# Estacion_Meteorologica_Feather__M0.net
KiCad netlist of a schematic drawn in Altium Designer
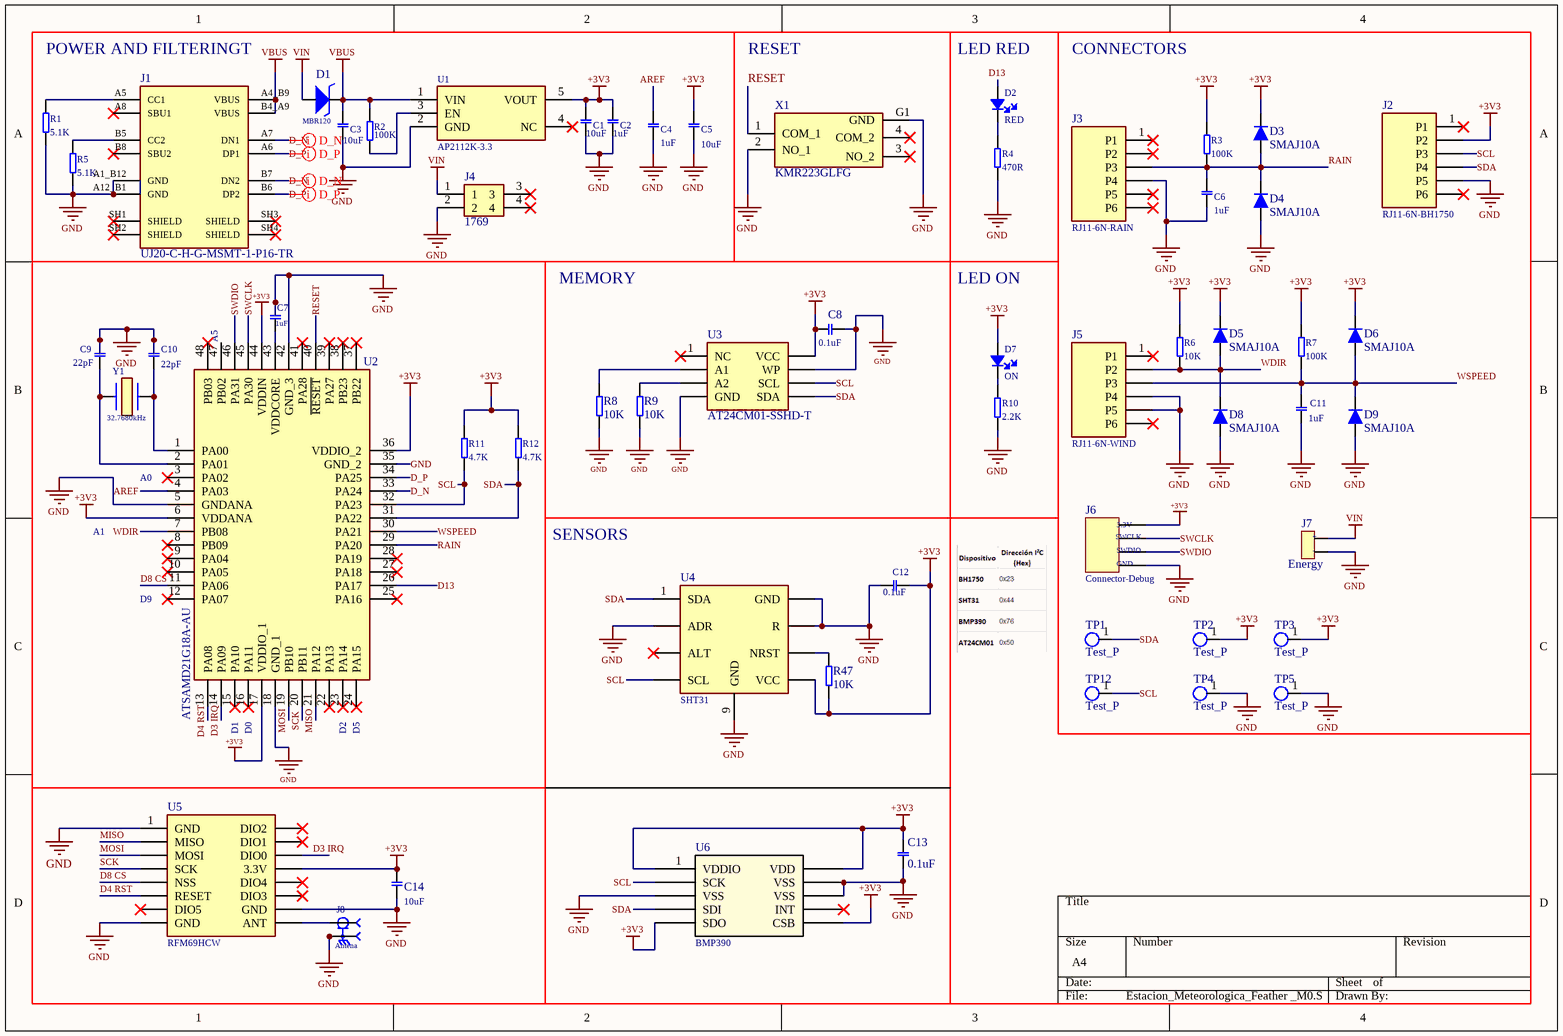
[diagram p0: Estacion_Meteorologica_Feather _M0.SchDoc]

(export (version "E")
  (design (tool "Eeschema 10.0.6"))
  (components
    (comp (ref "C1")
      (value "10uF")
      (footprint "CAPCP1608_0603")
      (description "Capacitor_10uF_0603")
      (libsource (lib "Estacion_Meteorologica_Final") (part "C0603X100J1GACAUTO"))
    )
    (comp (ref "C2")
      (value "1uF")
      (footprint "CAPCP1608_0603")
      (description "Capacitor_1uF_0603")
      (libsource (lib "Estacion_Meteorologica_Final") (part "C0603X105J4RACTU"))
    )
    (comp (ref "C3")
      (value "10uF")
      (footprint "CAPCP1608_0603")
      (description "Capacitor_10uF_0603")
      (libsource (lib "Estacion_Meteorologica_Final") (part "C0603X100J1GACAUTO"))
    )
    (comp (ref "C4")
      (value "1uF")
      (footprint "CAPCP1608_0603")
      (description "Capacitor_1uF_0603")
      (libsource (lib "Estacion_Meteorologica_Final") (part "C0603X105J4RACTU"))
    )
    (comp (ref "C5")
      (value "10uF")
      (footprint "CAPCP1608_0603")
      (description "Capacitor_10uF_0603")
      (libsource (lib "Estacion_Meteorologica_Final") (part "C0603X100J1GACAUTO"))
    )
    (comp (ref "C6")
      (value "1uF")
      (footprint "CAPCP1608_0603")
      (description "Capacitor_1uF_0603")
      (libsource (lib "Estacion_Meteorologica_Final") (part "C0603X105J4RACTU"))
    )
    (comp (ref "C7")
      (value "1uF")
      (footprint "CAPCP1608_0603")
      (description "Capacitor_1uF_0603")
      (libsource (lib "Estacion_Meteorologica_Final") (part "C0603X105J4RACTU"))
    )
    (comp (ref "C8")
      (value "0.1uF")
      (footprint "CAPCP1608_0603")
      (description "Capacitor_0.1uF_0603")
      (libsource (lib "Estacion_Meteorologica_Final") (part "06035C104K4T4A"))
    )
    (comp (ref "C9")
      (value "22pF")
      (footprint "CAPCP1608_0603")
      (description "Capacitor_22pF_0603")
      (libsource (lib "Estacion_Meteorologica_Final") (part "C0603C220J1GAC"))
    )
    (comp (ref "C10")
      (value "22pF")
      (footprint "CAPCP1608_0603")
      (description "Capacitor_22pF_0603")
      (libsource (lib "Estacion_Meteorologica_Final") (part "C0603C220J1GAC"))
    )
    (comp (ref "C11")
      (value "1uF")
      (footprint "CAPCP1608_0603")
      (description "Capacitor_1uF_0603")
      (libsource (lib "Estacion_Meteorologica_Final") (part "C0603X105J4RACTU"))
    )
    (comp (ref "C12")
      (value "0.1uF")
      (footprint "CAPCP1608_0603")
      (description "Capacitor_0.1uF_0603")
      (libsource (lib "Estacion_Meteorologica_Final") (part "06035C104K4T4A"))
    )
    (comp (ref "C13")
      (value "0.1uF")
      (footprint "CAPCP1608_0603")
      (description "Capacitor_0.1uF_0603")
      (libsource (lib "Estacion_Meteorologica_Final") (part "06035C104K4T4A"))
    )
    (comp (ref "C14")
      (value "10uF")
      (footprint "CAPCP1608_0603")
      (description "Capacitor_10uF_0603")
      (libsource (lib "Estacion_Meteorologica_Final") (part "C0603X100J1GACAUTO"))
    )
    (comp (ref "D1")
      (value "MBR120")
      (footprint "SODFL3616X98N")
      (description "Diodo_Zenner_Sod-123FL-2")
      (libsource (lib "Estacion_Meteorologica_Final") (part "MBR120ESFT3G"))
    )
    (comp (ref "D2")
      (value "RED")
      (footprint "DIODO_0603")
      (description "LED_NARANJA_0603")
      (libsource (lib "Estacion_Meteorologica_Final") (part "SML-D12D1WT86"))
    )
    (comp (ref "D3")
      (value "SMAJ10A")
      (footprint "DIOM4325X250N")
      (description "TVS Diode 10V 400W Unidirectional SMAJ10A (DO-214AC)")
      (libsource (lib "Estacion_Meteorologica_Final") (part "SMAJ10A"))
    )
    (comp (ref "D4")
      (value "SMAJ10A")
      (footprint "DIOM4325X250N")
      (description "TVS Diode 10V 400W Unidirectional SMAJ10A (DO-214AC)")
      (libsource (lib "Estacion_Meteorologica_Final") (part "SMAJ10A"))
    )
    (comp (ref "D5")
      (value "SMAJ10A")
      (footprint "DIOM4325X250N")
      (description "TVS Diode 10V 400W Unidirectional SMAJ10A (DO-214AC)")
      (libsource (lib "Estacion_Meteorologica_Final") (part "SMAJ10A"))
    )
    (comp (ref "D6")
      (value "SMAJ10A")
      (footprint "DIOM4325X250N")
      (description "TVS Diode 10V 400W Unidirectional SMAJ10A (DO-214AC)")
      (libsource (lib "Estacion_Meteorologica_Final") (part "SMAJ10A"))
    )
    (comp (ref "D7")
      (value "ON")
      (footprint "DIODO_0603")
      (description "LED_NARANJA_0603")
      (libsource (lib "Estacion_Meteorologica_Final") (part "SML-D12D1WT86"))
    )
    (comp (ref "D8")
      (value "SMAJ10A")
      (footprint "DIOM4325X250N")
      (description "TVS Diode 10V 400W Unidirectional SMAJ10A (DO-214AC)")
      (libsource (lib "Estacion_Meteorologica_Final") (part "SMAJ10A"))
    )
    (comp (ref "D9")
      (value "SMAJ10A")
      (footprint "DIOM4325X250N")
      (description "TVS Diode 10V 400W Unidirectional SMAJ10A (DO-214AC)")
      (libsource (lib "Estacion_Meteorologica_Final") (part "SMAJ10A"))
    )
    (comp (ref "J1")
      (value "UJ20-C-H-G-MSMT-1-P16-TR")
      (footprint "uJ20-C-H-G-MSMT-1-P16-TR")
      (description "Conector usb c")
      (libsource (lib "Estacion_Meteorologica_Final") (part "UJ20-C-H-G-MSMT-1-P16-TR"))
    )
    (comp (ref "J2")
      (value "RJ11-6N-BH1750")
      (footprint "TE_RJ11-6N-B")
      (description "6 Position 1 Port Right Angle RJ11 Low Profile Filtered EMI/RFI Modular Jack")
      (fields (field (name "MP") "RJ11-6N-B") (field (name "MF") "TE Connectivity"))
      (libsource (lib "Estacion_Meteorologica_Final") (part "RJ11-6N-B"))
    )
    (comp (ref "J3")
      (value "RJ11-6N-RAIN")
      (footprint "TE_RJ11-6N-B")
      (description "6 Position 1 Port Right Angle RJ11 Low Profile Filtered EMI/RFI Modular Jack")
      (fields (field (name "MP") "RJ11-6N-B") (field (name "MF") "TE Connectivity"))
      (libsource (lib "Estacion_Meteorologica_Final") (part "RJ11-6N-B"))
    )
    (comp (ref "J4")
      (value "1769")
      (footprint "1769_Conector_Bateria")
      (description "Adafruit Accessories JST-PH 2-pin SMT Right Angle Connect")
      (fields (field (name "MOUSER PART NUMBER") "485-1769"))
      (libsource (lib "Estacion_Meteorologica_Final") (part "1769"))
    )
    (comp (ref "J5")
      (value "RJ11-6N-WIND")
      (footprint "TE_RJ11-6N-B")
      (description "6 Position 1 Port Right Angle RJ11 Low Profile Filtered EMI/RFI Modular Jack")
      (fields (field (name "MP") "RJ11-6N-B") (field (name "MF") "TE Connectivity"))
      (libsource (lib "Estacion_Meteorologica_Final") (part "RJ11-6N-B"))
    )
    (comp (ref "J6")
      (value "Connector-Debug")
      (footprint "HDR1X4")
      (libsource (lib "Estacion_Meteorologica_Final") (part "Connector_04_debug"))
    )
    (comp (ref "J7")
      (value "Energy")
      (footprint "HDR1X2_2")
      (description "Conector de gestor de carga")
      (libsource (lib "Estacion_Meteorologica_Final") (part "Connector_energy"))
    )
    (comp (ref "J8")
      (value "Antena")
      (footprint "SAMTEC_RSP-122811-01")
      (description "U.FL (UMCC), IPEX MHF1 Connector Receptacle, Male Pin 50Ohm Surface Mount Solder")
      (fields (field (name "MP") "RSP-122811-01"))
      (libsource (lib "Estacion_Meteorologica_Final") (part "RSP-122811-01"))
    )
    (comp (ref "R1")
      (value "5.1K")
      (footprint "RESC1608_0603")
      (description "Resistencia_5.1K_0603")
      (libsource (lib "Estacion_Meteorologica_Final") (part "RCA06035K10JNEA"))
    )
    (comp (ref "R2")
      (value "100K")
      (footprint "RESC1608_0603")
      (description "Resistencia_100K_0603")
      (libsource (lib "Estacion_Meteorologica_Final") (part "RCA0603100KFKEAHP"))
    )
    (comp (ref "R3")
      (value "100K")
      (footprint "RESC1608_0603")
      (description "Resistencia_100K_0603")
      (libsource (lib "Estacion_Meteorologica_Final") (part "RCA0603100KFKEAHP"))
    )
    (comp (ref "R4")
      (value "470R")
      (footprint "RESC1608_0603")
      (description "Resistencia_470R_0603")
      (libsource (lib "Estacion_Meteorologica_Final") (part "RCA0603470RFKEA"))
    )
    (comp (ref "R5")
      (value "5.1K")
      (footprint "RESC1608_0603")
      (description "Resistencia_5.1K_0603")
      (libsource (lib "Estacion_Meteorologica_Final") (part "RCA06035K10JNEA"))
    )
    (comp (ref "R6")
      (value "10K")
      (footprint "RESC1608_0603")
      (description "Resistencia_10K_0603")
      (libsource (lib "Estacion_Meteorologica_Final") (part "RCA060310K0JNEA"))
    )
    (comp (ref "R7")
      (value "100K")
      (footprint "RESC1608_0603")
      (description "Resistencia_100K_0603")
      (libsource (lib "Estacion_Meteorologica_Final") (part "RCA0603100KFKEAHP"))
    )
    (comp (ref "R8")
      (value "10K")
      (footprint "RESC1608_0603")
      (description "Resistencia_10K_0603")
      (libsource (lib "Estacion_Meteorologica_Final") (part "RCA060310K0JNEA"))
    )
    (comp (ref "R9")
      (value "10K")
      (footprint "RESC1608_0603")
      (description "Resistencia_10K_0603")
      (libsource (lib "Estacion_Meteorologica_Final") (part "RCA060310K0JNEA"))
    )
    (comp (ref "R10")
      (value "2.2K")
      (footprint "RESC1608_0603")
      (description "Resistencia_2.2K_0603")
      (libsource (lib "Estacion_Meteorologica_Final") (part "RCA06032K21FKTA"))
    )
    (comp (ref "R11")
      (value "4.7K")
      (footprint "RESC1608_0603")
      (description "Resistencia_4.7K_0603")
      (libsource (lib "Estacion_Meteorologica_Final") (part "RCA06034K70FKEA"))
    )
    (comp (ref "R12")
      (value "4.7K")
      (footprint "RESC1608_0603")
      (description "Resistencia_4.7K_0603")
      (libsource (lib "Estacion_Meteorologica_Final") (part "RCA06034K70FKEA"))
    )
    (comp (ref "R47")
      (value "10K")
      (footprint "RESC1608_0603")
      (description "Resistencia_10K_0603")
      (libsource (lib "Estacion_Meteorologica_Final") (part "RCA060310K0JNEA"))
    )
    (comp (ref "TP1")
      (value "Test_P")
      (footprint "Test_point")
      (libsource (lib "Estacion_Meteorologica_Final") (part "Test_point"))
    )
    (comp (ref "TP2")
      (value "Test_P")
      (footprint "Test_point")
      (libsource (lib "Estacion_Meteorologica_Final") (part "Test_point"))
    )
    (comp (ref "TP3")
      (value "Test_P")
      (footprint "Test_point")
      (libsource (lib "Estacion_Meteorologica_Final") (part "Test_point"))
    )
    (comp (ref "TP4")
      (value "Test_P")
      (footprint "Test_point")
      (libsource (lib "Estacion_Meteorologica_Final") (part "Test_point"))
    )
    (comp (ref "TP5")
      (value "Test_P")
      (footprint "Test_point")
      (libsource (lib "Estacion_Meteorologica_Final") (part "Test_point"))
    )
    (comp (ref "TP12")
      (value "Test_P")
      (footprint "Test_point")
      (libsource (lib "Estacion_Meteorologica_Final") (part "Test_point"))
    )
    (comp (ref "U1")
      (value "AP2112K-3.3")
      (footprint "SOT-23-5")
      (fields
        (field (name "MOUSER PART NUMBER") "621-AP2112K-3.3TRG1")
        (field (name "MANUFACTURER_PART_NUMBER") "AP2112K-3.3TRG1")
      )
      (libsource (lib "Estacion_Meteorologica_Final") (part "AP2112K-3.3TRG1"))
    )
    (comp (ref "U2")
      (value "ATSAMD21G18A-AU")
      (footprint "QFP-48N")
      (description "ARM Microcontrollers - MCU 256KB 32KB 48TQFP GRN1.6-3.6V48MHz")
      (fields (field (name "MOUSER PART NUMBER") "556-ATSAMD21G18A-AU"))
      (libsource (lib "Estacion_Meteorologica_Final") (part "ATSAMD21G18A-AU"))
    )
    (comp (ref "U3")
      (value "AT24CM01-SSHD-T")
      (footprint "SOIC-8N")
      (description "EEPROM SERIAL EEPROM, 1M 2-WIR-8 SOIC")
      (fields (field (name "MOUSER PART NUMBER") "556-AT24CM01-SSHD-T"))
      (libsource (lib "Estacion_Meteorologica_Final") (part "AT24CM01-SSHD-T"))
    )
    (comp (ref "U4")
      (value "SHT31")
      (footprint "SON50P250X250X90-9T110X180N")
      (description "Humidity Temperature Sensor 0 ~ 100% RH Analog Voltage Â±2% RH 8s Surface Mount")
      (fields (field (name "MF") "Sensirion AG"))
      (libsource (lib "Estacion_Meteorologica_Final") (part "SHT31"))
    )
    (comp (ref "U5")
      (value "RFM69HCW")
      (footprint "COM-13909")
      (description "Rfm69hcw Wireless Transceiver 91")
      (fields (field (name "MP") "COM-13909"))
      (libsource (lib "Estacion_Meteorologica_Final") (part "COM-13909"))
    )
    (comp (ref "U6")
      (value "BMP390")
      (footprint "10LGA_2X2X0p75_BOS-M")
      (description "Barometric Pressure Sensor, I2C/SPI, 300-1250 hPa")
      (libsource (lib "Estacion_Meteorologica_Final") (part "BMP390"))
    )
    (comp (ref "X1")
      (value "KMR223GLFG")
      (footprint "KMR223GLFG_Boton")
      (description "Tactile Switch SPST-NO Top Actuated Surface Mount")
      (fields (field (name "MOUSER PART NUMBER") "611-KMR223GLFG"))
      (libsource (lib "Estacion_Meteorologica_Final") (part "KMR223GLFG_1"))
    )
    (comp (ref "Y1")
      (value "32.7680kHz")
      (footprint "XTAL 830050789")
      (description "XTAL 32.7680kHz 20ppm 2.0 x 1.2mm")
      (libsource (lib "Estacion_Meteorologica_Final") (part "830050789"))
    )
  )
  (nets
    (net (code "1") (name "+3V3") (class "Default")
      (node (ref "C1") (pin "2") (pinfunction "2_2") (pintype "passive"))
      (node (ref "C12") (pin "2") (pinfunction "2_2") (pintype "passive"))
      (node (ref "C13") (pin "2") (pinfunction "2_2") (pintype "passive"))
      (node (ref "C14") (pin "2") (pinfunction "2_2") (pintype "passive"))
      (node (ref "C2") (pin "2") (pinfunction "2_2") (pintype "passive"))
      (node (ref "C5") (pin "2") (pinfunction "2_2") (pintype "passive"))
      (node (ref "C8") (pin "1") (pinfunction "1_1") (pintype "passive"))
      (node (ref "D3") (pin "2") (pinfunction "2_2") (pintype "passive"))
      (node (ref "D5") (pin "2") (pinfunction "2_2") (pintype "passive"))
      (node (ref "D6") (pin "2") (pinfunction "2_2") (pintype "passive"))
      (node (ref "D7") (pin "1") (pinfunction "1_1") (pintype "passive"))
      (node (ref "J2") (pin "2") (pinfunction "P2_2") (pintype "passive"))
      (node (ref "J6") (pin "1") (pinfunction "1_1") (pintype "passive"))
      (node (ref "R11") (pin "2") (pinfunction "2_2") (pintype "passive"))
      (node (ref "R12") (pin "2") (pinfunction "2_2") (pintype "passive"))
      (node (ref "R3") (pin "2") (pinfunction "2_2") (pintype "passive"))
      (node (ref "R47") (pin "1") (pinfunction "1_1") (pintype "passive"))
      (node (ref "R6") (pin "2") (pinfunction "2_2") (pintype "passive"))
      (node (ref "R7") (pin "2") (pinfunction "2_2") (pintype "passive"))
      (node (ref "TP2") (pin "1") (pinfunction "1_1") (pintype "passive"))
      (node (ref "TP3") (pin "1") (pinfunction "1_1") (pintype "passive"))
      (node (ref "U1") (pin "5") (pinfunction "VOUT_5") (pintype "passive"))
      (node (ref "U2") (pin "17") (pinfunction "VDDIO_1_17") (pintype "passive"))
      (node (ref "U2") (pin "36") (pinfunction "VDDIO_2_36") (pintype "passive"))
      (node (ref "U2") (pin "44") (pinfunction "VDDIN_44") (pintype "passive"))
      (node (ref "U2") (pin "6") (pinfunction "VDDANA_6") (pintype "passive"))
      (node (ref "U3") (pin "8") (pinfunction "VCC_8") (pintype "passive"))
      (node (ref "U4") (pin "5") (pinfunction "VCC_5") (pintype "passive"))
      (node (ref "U5") (pin "13") (pinfunction "3.3V_13") (pintype "passive"))
      (node (ref "U6") (pin "1") (pinfunction "VDDIO_1") (pintype "passive"))
      (node (ref "U6") (pin "10") (pinfunction "VDD_10") (pintype "passive"))
      (node (ref "U6") (pin "5") (pinfunction "SDO_5") (pintype "passive"))
      (node (ref "U6") (pin "6") (pinfunction "CSB_6") (pintype "passive"))
    )
    (net (code "2") (name "/AREF") (class "Default")
      (node (ref "C4") (pin "2") (pinfunction "2_2") (pintype "passive"))
      (node (ref "U2") (pin "4") (pinfunction "PA03_4") (pintype "passive"))
    )
    (net (code "3") (name "/D3 IRQ") (class "Default")
      (node (ref "U2") (pin "14") (pinfunction "PA09_14") (pintype "passive"))
      (node (ref "U5") (pin "14") (pinfunction "DIO0_14") (pintype "passive"))
    )
    (net (code "4") (name "/D4 RST") (class "Default")
      (node (ref "U2") (pin "13") (pinfunction "PA08_13") (pintype "passive"))
      (node (ref "U5") (pin "6") (pinfunction "RESET_6") (pintype "passive"))
    )
    (net (code "5") (name "/D8 CS") (class "Default")
      (node (ref "U2") (pin "11") (pinfunction "PA06_11") (pintype "passive"))
      (node (ref "U5") (pin "5") (pinfunction "NSS_5") (pintype "passive"))
    )
    (net (code "6") (name "/D13") (class "Default")
      (node (ref "D2") (pin "1") (pinfunction "1_1") (pintype "passive"))
      (node (ref "U2") (pin "26") (pinfunction "PA17_26") (pintype "passive"))
    )
    (net (code "7") (name "/D_N") (class "Default")
      (node (ref "J1") (pin "A7") (pinfunction "DN1_A7") (pintype "passive"))
      (node (ref "J1") (pin "B7") (pinfunction "DN2_B7") (pintype "passive"))
      (node (ref "U2") (pin "33") (pinfunction "PA24_33") (pintype "passive"))
    )
    (net (code "8") (name "/D_P") (class "Default")
      (node (ref "J1") (pin "A6") (pinfunction "DP1_A6") (pintype "passive"))
      (node (ref "J1") (pin "B6") (pinfunction "DP2_B6") (pintype "passive"))
      (node (ref "U2") (pin "34") (pinfunction "PA25_34") (pintype "passive"))
    )
    (net (code "9") (name "/MISO") (class "Default")
      (node (ref "U2") (pin "21") (pinfunction "PA12_21") (pintype "passive"))
      (node (ref "U5") (pin "2") (pinfunction "MISO_2") (pintype "passive"))
    )
    (net (code "10") (name "/MOSI") (class "Default")
      (node (ref "U2") (pin "19") (pinfunction "PB10_19") (pintype "passive"))
      (node (ref "U5") (pin "3") (pinfunction "MOSI_3") (pintype "passive"))
    )
    (net (code "11") (name "/RAIN") (class "Default")
      (node (ref "C6") (pin "2") (pinfunction "2_2") (pintype "passive"))
      (node (ref "D3") (pin "1") (pinfunction "21_1") (pintype "passive"))
      (node (ref "D4") (pin "2") (pinfunction "2_2") (pintype "passive"))
      (node (ref "J3") (pin "3") (pinfunction "P3_3") (pintype "passive"))
      (node (ref "R3") (pin "1") (pinfunction "1_1") (pintype "passive"))
      (node (ref "U2") (pin "29") (pinfunction "PA20_29") (pintype "passive"))
    )
    (net (code "12") (name "/RESET") (class "Default")
      (node (ref "U2") (pin "40") (pinfunction "~{RESET}_40") (pintype "passive"))
      (node (ref "X1") (pin "1") (pinfunction "COM_1_1") (pintype "passive"))
    )
    (net (code "13") (name "/SCK") (class "Default")
      (node (ref "U2") (pin "20") (pinfunction "PB11_20") (pintype "passive"))
      (node (ref "U5") (pin "4") (pinfunction "SCK_4") (pintype "passive"))
    )
    (net (code "14") (name "/SCL") (class "Default")
      (node (ref "J2") (pin "3") (pinfunction "P3_3") (pintype "passive"))
      (node (ref "R11") (pin "1") (pinfunction "1_1") (pintype "passive"))
      (node (ref "TP12") (pin "1") (pinfunction "1_1") (pintype "passive"))
      (node (ref "U2") (pin "32") (pinfunction "PA23_32") (pintype "passive"))
      (node (ref "U3") (pin "6") (pinfunction "SCL_6") (pintype "passive"))
      (node (ref "U4") (pin "4") (pinfunction "SCL_4") (pintype "passive"))
      (node (ref "U6") (pin "2") (pinfunction "SCK_2") (pintype "passive"))
    )
    (net (code "15") (name "/SDA") (class "Default")
      (node (ref "J2") (pin "4") (pinfunction "P4_4") (pintype "passive"))
      (node (ref "R12") (pin "1") (pinfunction "1_1") (pintype "passive"))
      (node (ref "TP1") (pin "1") (pinfunction "1_1") (pintype "passive"))
      (node (ref "U2") (pin "31") (pinfunction "PA22_31") (pintype "passive"))
      (node (ref "U3") (pin "5") (pinfunction "SDA_5") (pintype "passive"))
      (node (ref "U4") (pin "1") (pinfunction "SDA_1") (pintype "passive"))
      (node (ref "U6") (pin "4") (pinfunction "SDI_4") (pintype "passive"))
    )
    (net (code "16") (name "/SWCLK") (class "Default")
      (node (ref "J6") (pin "2") (pinfunction "2_2") (pintype "passive"))
      (node (ref "U2") (pin "45") (pinfunction "PA30_45") (pintype "passive"))
    )
    (net (code "17") (name "/SWDIO") (class "Default")
      (node (ref "J6") (pin "3") (pinfunction "3_3") (pintype "passive"))
      (node (ref "U2") (pin "46") (pinfunction "PA31_46") (pintype "passive"))
    )
    (net (code "18") (name "/WDIR") (class "Default")
      (node (ref "D5") (pin "1") (pinfunction "21_1") (pintype "passive"))
      (node (ref "D8") (pin "2") (pinfunction "2_2") (pintype "passive"))
      (node (ref "J5") (pin "2") (pinfunction "P2_2") (pintype "passive"))
      (node (ref "R6") (pin "1") (pinfunction "1_1") (pintype "passive"))
      (node (ref "U2") (pin "7") (pinfunction "PB08_7") (pintype "passive"))
    )
    (net (code "19") (name "/WSPEED") (class "Default")
      (node (ref "C11") (pin "2") (pinfunction "2_2") (pintype "passive"))
      (node (ref "D6") (pin "1") (pinfunction "21_1") (pintype "passive"))
      (node (ref "D9") (pin "2") (pinfunction "2_2") (pintype "passive"))
      (node (ref "J5") (pin "3") (pinfunction "P3_3") (pintype "passive"))
      (node (ref "R7") (pin "1") (pinfunction "1_1") (pintype "passive"))
      (node (ref "U2") (pin "30") (pinfunction "PA21_30") (pintype "passive"))
    )
    (net (code "20") (name "GND") (class "Default")
      (node (ref "C1") (pin "1") (pinfunction "1_1") (pintype "passive"))
      (node (ref "C10") (pin "2") (pinfunction "2_2") (pintype "passive"))
      (node (ref "C11") (pin "1") (pinfunction "1_1") (pintype "passive"))
      (node (ref "C12") (pin "1") (pinfunction "1_1") (pintype "passive"))
      (node (ref "C13") (pin "1") (pinfunction "1_1") (pintype "passive"))
      (node (ref "C14") (pin "1") (pinfunction "1_1") (pintype "passive"))
      (node (ref "C2") (pin "1") (pinfunction "1_1") (pintype "passive"))
      (node (ref "C3") (pin "1") (pinfunction "1_1") (pintype "passive"))
      (node (ref "C4") (pin "1") (pinfunction "1_1") (pintype "passive"))
      (node (ref "C5") (pin "1") (pinfunction "1_1") (pintype "passive"))
      (node (ref "C6") (pin "1") (pinfunction "1_1") (pintype "passive"))
      (node (ref "C7") (pin "2") (pinfunction "2_2") (pintype "passive"))
      (node (ref "C8") (pin "2") (pinfunction "2_2") (pintype "passive"))
      (node (ref "C9") (pin "2") (pinfunction "2_2") (pintype "passive"))
      (node (ref "D4") (pin "1") (pinfunction "21_1") (pintype "passive"))
      (node (ref "D8") (pin "1") (pinfunction "21_1") (pintype "passive"))
      (node (ref "D9") (pin "1") (pinfunction "21_1") (pintype "passive"))
      (node (ref "J1") (pin "A12_B1") (pinfunction "GND_A12_B1") (pintype "passive"))
      (node (ref "J1") (pin "A1_B12") (pinfunction "GND_A1_B12") (pintype "passive"))
      (node (ref "J2") (pin "5") (pinfunction "P5_5") (pintype "passive"))
      (node (ref "J3") (pin "4") (pinfunction "P4_4") (pintype "passive"))
      (node (ref "J4") (pin "2") (pinfunction "2_2") (pintype "passive"))
      (node (ref "J5") (pin "4") (pinfunction "P4_4") (pintype "passive"))
      (node (ref "J5") (pin "5") (pinfunction "P5_5") (pintype "passive"))
      (node (ref "J6") (pin "4") (pinfunction "4_4") (pintype "passive"))
      (node (ref "J7") (pin "2") (pinfunction "2_2") (pintype "passive"))
      (node (ref "J8") (pin "G1") (pinfunction "GND_G1") (pintype "passive"))
      (node (ref "J8") (pin "G2") (pinfunction "GND_G2") (pintype "passive"))
      (node (ref "R1") (pin "1") (pinfunction "1_1") (pintype "passive"))
      (node (ref "R10") (pin "2") (pinfunction "2_2") (pintype "passive"))
      (node (ref "R4") (pin "1") (pinfunction "1_1") (pintype "passive"))
      (node (ref "R5") (pin "1") (pinfunction "1_1") (pintype "passive"))
      (node (ref "R8") (pin "1") (pinfunction "1_1") (pintype "passive"))
      (node (ref "R9") (pin "1") (pinfunction "1_1") (pintype "passive"))
      (node (ref "TP4") (pin "1") (pinfunction "1_1") (pintype "passive"))
      (node (ref "TP5") (pin "1") (pinfunction "1_1") (pintype "passive"))
      (node (ref "U1") (pin "2") (pinfunction "GND_2") (pintype "passive"))
      (node (ref "U2") (pin "18") (pinfunction "GND_1_18") (pintype "passive"))
      (node (ref "U2") (pin "35") (pinfunction "GND_2_35") (pintype "passive"))
      (node (ref "U2") (pin "42") (pinfunction "GND_3_42") (pintype "passive"))
      (node (ref "U2") (pin "5") (pinfunction "GNDANA_5") (pintype "passive"))
      (node (ref "U3") (pin "4") (pinfunction "GND_4") (pintype "passive"))
      (node (ref "U3") (pin "7") (pinfunction "WP_7") (pintype "passive"))
      (node (ref "U4") (pin "2") (pinfunction "ADR_2") (pintype "passive"))
      (node (ref "U4") (pin "7") (pinfunction "R_7") (pintype "passive"))
      (node (ref "U4") (pin "8") (pinfunction "GND_8") (pintype "passive"))
      (node (ref "U4") (pin "9") (pinfunction "GND_9") (pintype "passive"))
      (node (ref "U5") (pin "1") (pinfunction "GND_1") (pintype "passive"))
      (node (ref "U5") (pin "10") (pinfunction "GND_10") (pintype "passive"))
      (node (ref "U5") (pin "8") (pinfunction "GND_8") (pintype "passive"))
      (node (ref "U6") (pin "3") (pinfunction "VSS_3") (pintype "passive"))
      (node (ref "U6") (pin "8") (pinfunction "VSS_8") (pintype "passive"))
      (node (ref "U6") (pin "9") (pinfunction "VSS_9") (pintype "passive"))
      (node (ref "X1") (pin "2") (pinfunction "NO_1_2") (pintype "passive"))
      (node (ref "X1") (pin "G1") (pinfunction "GND_G1") (pintype "passive"))
    )
    (net (code "21") (name "Net-(D2-Pad2)") (class "Default")
      (node (ref "D2") (pin "2") (pinfunction "2_2") (pintype "passive"))
      (node (ref "R4") (pin "2") (pinfunction "2_2") (pintype "passive"))
    )
    (net (code "22") (name "Net-(D7-Pad2)") (class "Default")
      (node (ref "D7") (pin "2") (pinfunction "2_2") (pintype "passive"))
      (node (ref "R10") (pin "1") (pinfunction "1_1") (pintype "passive"))
    )
    (net (code "23") (name "Net-(J1-CC1)") (class "Default")
      (node (ref "J1") (pin "A5") (pinfunction "CC1_A5") (pintype "passive"))
      (node (ref "R1") (pin "2") (pinfunction "2_2") (pintype "passive"))
    )
    (net (code "24") (name "Net-(J1-CC2)") (class "Default")
      (node (ref "J1") (pin "B5") (pinfunction "CC2_B5") (pintype "passive"))
      (node (ref "R5") (pin "2") (pinfunction "2_2") (pintype "passive"))
    )
    (net (code "25") (name "Net-(U1-EN)") (class "Default")
      (node (ref "R2") (pin "1") (pinfunction "1_1") (pintype "passive"))
      (node (ref "U1") (pin "3") (pinfunction "EN_3") (pintype "passive"))
    )
    (net (code "26") (name "Net-(U2-PA00)") (class "Default")
      (node (ref "C10") (pin "1") (pinfunction "1_1") (pintype "passive"))
      (node (ref "U2") (pin "1") (pinfunction "PA00_1") (pintype "passive"))
      (node (ref "Y1") (pin "2") (pinfunction "2_2") (pintype "passive"))
    )
    (net (code "27") (name "Net-(U2-PA01)") (class "Default")
      (node (ref "C9") (pin "1") (pinfunction "1_1") (pintype "passive"))
      (node (ref "U2") (pin "2") (pinfunction "PA01_2") (pintype "passive"))
      (node (ref "Y1") (pin "1") (pinfunction "1_1") (pintype "passive"))
    )
    (net (code "28") (name "Net-(U2-VDDCORE)") (class "Default")
      (node (ref "C7") (pin "1") (pinfunction "1_1") (pintype "passive"))
      (node (ref "U2") (pin "43") (pinfunction "VDDCORE_43") (pintype "passive"))
    )
    (net (code "29") (name "Net-(U3-A1)") (class "Default")
      (node (ref "R8") (pin "2") (pinfunction "2_2") (pintype "passive"))
      (node (ref "U3") (pin "2") (pinfunction "A1_2") (pintype "passive"))
    )
    (net (code "30") (name "Net-(U3-A2)") (class "Default")
      (node (ref "R9") (pin "2") (pinfunction "2_2") (pintype "passive"))
      (node (ref "U3") (pin "3") (pinfunction "A2_3") (pintype "passive"))
    )
    (net (code "31") (name "Net-(U4-NRST)") (class "Default")
      (node (ref "R47") (pin "2") (pinfunction "2_2") (pintype "passive"))
      (node (ref "U4") (pin "6") (pinfunction "NRST_6") (pintype "passive"))
    )
    (net (code "32") (name "Net-(U5-ANT)") (class "Default")
      (node (ref "J8") (pin "1") (pinfunction "1_1") (pintype "passive"))
      (node (ref "U5") (pin "9") (pinfunction "ANT_9") (pintype "passive"))
    )
    (net (code "33") (name "VBUS") (class "Default")
      (node (ref "C3") (pin "2") (pinfunction "2_2") (pintype "passive"))
      (node (ref "D1") (pin "2") (pinfunction "2_2") (pintype "passive"))
      (node (ref "J1") (pin "A4_B9") (pinfunction "VBUS_A4_B9") (pintype "passive"))
      (node (ref "J1") (pin "B4_A9") (pinfunction "VBUS_B4_A9") (pintype "passive"))
      (node (ref "R2") (pin "2") (pinfunction "2_2") (pintype "passive"))
      (node (ref "U1") (pin "1") (pinfunction "VIN_1") (pintype "passive"))
    )
    (net (code "34") (name "VIN") (class "Default")
      (node (ref "D1") (pin "1") (pinfunction "1_1") (pintype "passive"))
      (node (ref "J4") (pin "1") (pinfunction "1_1") (pintype "passive"))
      (node (ref "J7") (pin "1") (pinfunction "1_1") (pintype "passive"))
    )
    (net (code "35") (name "unconnected-(J1-SBU1-PadA8)") (class "Default")
      (node (ref "J1") (pin "A8") (pinfunction "SBU1_A8") (pintype "passive+no_connect"))
    )
    (net (code "36") (name "unconnected-(J1-SBU2-PadB8)") (class "Default")
      (node (ref "J1") (pin "B8") (pinfunction "SBU2_B8") (pintype "passive+no_connect"))
    )
    (net (code "37") (name "unconnected-(J1-SHIELD-PadSH1)") (class "Default")
      (node (ref "J1") (pin "SH1") (pinfunction "SHIELD_SH1") (pintype "passive+no_connect"))
    )
    (net (code "38") (name "unconnected-(J1-SHIELD-PadSH2)") (class "Default")
      (node (ref "J1") (pin "SH2") (pinfunction "SHIELD_SH2") (pintype "passive+no_connect"))
    )
    (net (code "39") (name "unconnected-(J1-SHIELD-PadSH3)") (class "Default")
      (node (ref "J1") (pin "SH3") (pinfunction "SHIELD_SH3") (pintype "passive+no_connect"))
    )
    (net (code "40") (name "unconnected-(J1-SHIELD-PadSH4)") (class "Default")
      (node (ref "J1") (pin "SH4") (pinfunction "SHIELD_SH4") (pintype "passive+no_connect"))
    )
    (net (code "41") (name "unconnected-(J2-P1-Pad1)") (class "Default")
      (node (ref "J2") (pin "1") (pinfunction "P1_1") (pintype "passive+no_connect"))
    )
    (net (code "42") (name "unconnected-(J2-P6-Pad6)") (class "Default")
      (node (ref "J2") (pin "6") (pinfunction "P6_6") (pintype "passive+no_connect"))
    )
    (net (code "43") (name "unconnected-(J3-P1-Pad1)") (class "Default")
      (node (ref "J3") (pin "1") (pinfunction "P1_1") (pintype "passive+no_connect"))
    )
    (net (code "44") (name "unconnected-(J3-P2-Pad2)") (class "Default")
      (node (ref "J3") (pin "2") (pinfunction "P2_2") (pintype "passive+no_connect"))
    )
    (net (code "45") (name "unconnected-(J3-P5-Pad5)") (class "Default")
      (node (ref "J3") (pin "5") (pinfunction "P5_5") (pintype "passive+no_connect"))
    )
    (net (code "46") (name "unconnected-(J3-P6-Pad6)") (class "Default")
      (node (ref "J3") (pin "6") (pinfunction "P6_6") (pintype "passive+no_connect"))
    )
    (net (code "47") (name "unconnected-(J4-Pad3)") (class "Default")
      (node (ref "J4") (pin "3") (pinfunction "3_3") (pintype "passive+no_connect"))
    )
    (net (code "48") (name "unconnected-(J4-Pad4)") (class "Default")
      (node (ref "J4") (pin "4") (pinfunction "4_4") (pintype "passive+no_connect"))
    )
    (net (code "49") (name "unconnected-(J5-P1-Pad1)") (class "Default")
      (node (ref "J5") (pin "1") (pinfunction "P1_1") (pintype "passive+no_connect"))
    )
    (net (code "50") (name "unconnected-(J5-P6-Pad6)") (class "Default")
      (node (ref "J5") (pin "6") (pinfunction "P6_6") (pintype "passive+no_connect"))
    )
    (net (code "51") (name "unconnected-(U1-NC-Pad4)") (class "Default")
      (node (ref "U1") (pin "4") (pinfunction "NC_4") (pintype "passive+no_connect"))
    )
    (net (code "52") (name "unconnected-(U2-PA02-Pad3)") (class "Default")
      (node (ref "U2") (pin "3") (pinfunction "PA02_3") (pintype "passive+no_connect"))
    )
    (net (code "53") (name "unconnected-(U2-PA04-Pad9)") (class "Default")
      (node (ref "U2") (pin "9") (pinfunction "PA04_9") (pintype "passive+no_connect"))
    )
    (net (code "54") (name "unconnected-(U2-PA05-Pad10)") (class "Default")
      (node (ref "U2") (pin "10") (pinfunction "PA05_10") (pintype "passive+no_connect"))
    )
    (net (code "55") (name "unconnected-(U2-PA07-Pad12)") (class "Default")
      (node (ref "U2") (pin "12") (pinfunction "PA07_12") (pintype "passive+no_connect"))
    )
    (net (code "56") (name "unconnected-(U2-PA10-Pad15)") (class "Default")
      (node (ref "U2") (pin "15") (pinfunction "PA10_15") (pintype "passive+no_connect"))
    )
    (net (code "57") (name "unconnected-(U2-PA11-Pad16)") (class "Default")
      (node (ref "U2") (pin "16") (pinfunction "PA11_16") (pintype "passive+no_connect"))
    )
    (net (code "58") (name "unconnected-(U2-PA13-Pad22)") (class "Default")
      (node (ref "U2") (pin "22") (pinfunction "PA13_22") (pintype "passive+no_connect"))
    )
    (net (code "59") (name "unconnected-(U2-PA14-Pad23)") (class "Default")
      (node (ref "U2") (pin "23") (pinfunction "PA14_23") (pintype "passive+no_connect"))
    )
    (net (code "60") (name "unconnected-(U2-PA15-Pad24)") (class "Default")
      (node (ref "U2") (pin "24") (pinfunction "PA15_24") (pintype "passive+no_connect"))
    )
    (net (code "61") (name "unconnected-(U2-PA16-Pad25)") (class "Default")
      (node (ref "U2") (pin "25") (pinfunction "PA16_25") (pintype "passive+no_connect"))
    )
    (net (code "62") (name "unconnected-(U2-PA18-Pad27)") (class "Default")
      (node (ref "U2") (pin "27") (pinfunction "PA18_27") (pintype "passive+no_connect"))
    )
    (net (code "63") (name "unconnected-(U2-PA19-Pad28)") (class "Default")
      (node (ref "U2") (pin "28") (pinfunction "PA19_28") (pintype "passive+no_connect"))
    )
    (net (code "64") (name "unconnected-(U2-PA27-Pad39)") (class "Default")
      (node (ref "U2") (pin "39") (pinfunction "PA27_39") (pintype "passive+no_connect"))
    )
    (net (code "65") (name "unconnected-(U2-PA28-Pad41)") (class "Default")
      (node (ref "U2") (pin "41") (pinfunction "PA28_41") (pintype "passive+no_connect"))
    )
    (net (code "66") (name "unconnected-(U2-PB02-Pad47)") (class "Default")
      (node (ref "U2") (pin "47") (pinfunction "PB02_47") (pintype "passive"))
    )
    (net (code "67") (name "unconnected-(U2-PB03-Pad48)") (class "Default")
      (node (ref "U2") (pin "48") (pinfunction "PB03_48") (pintype "passive+no_connect"))
    )
    (net (code "68") (name "unconnected-(U2-PB09-Pad8)") (class "Default")
      (node (ref "U2") (pin "8") (pinfunction "PB09_8") (pintype "passive+no_connect"))
    )
    (net (code "69") (name "unconnected-(U2-PB22-Pad37)") (class "Default")
      (node (ref "U2") (pin "37") (pinfunction "PB22_37") (pintype "passive+no_connect"))
    )
    (net (code "70") (name "unconnected-(U2-PB23-Pad38)") (class "Default")
      (node (ref "U2") (pin "38") (pinfunction "PB23_38") (pintype "passive+no_connect"))
    )
    (net (code "71") (name "unconnected-(U3-NC-Pad1)") (class "Default")
      (node (ref "U3") (pin "1") (pinfunction "NC_1") (pintype "passive+no_connect"))
    )
    (net (code "72") (name "unconnected-(U4-ALT-Pad3)") (class "Default")
      (node (ref "U4") (pin "3") (pinfunction "ALT_3") (pintype "passive+no_connect"))
    )
    (net (code "73") (name "unconnected-(U5-DIO1-Pad15)") (class "Default")
      (node (ref "U5") (pin "15") (pinfunction "DIO1_15") (pintype "passive+no_connect"))
    )
    (net (code "74") (name "unconnected-(U5-DIO2-Pad16)") (class "Default")
      (node (ref "U5") (pin "16") (pinfunction "DIO2_16") (pintype "passive+no_connect"))
    )
    (net (code "75") (name "unconnected-(U5-DIO3-Pad11)") (class "Default")
      (node (ref "U5") (pin "11") (pinfunction "DIO3_11") (pintype "passive+no_connect"))
    )
    (net (code "76") (name "unconnected-(U5-DIO4-Pad12)") (class "Default")
      (node (ref "U5") (pin "12") (pinfunction "DIO4_12") (pintype "passive+no_connect"))
    )
    (net (code "77") (name "unconnected-(U5-DIO5-Pad7)") (class "Default")
      (node (ref "U5") (pin "7") (pinfunction "DIO5_7") (pintype "passive+no_connect"))
    )
    (net (code "78") (name "unconnected-(U6-INT-Pad7)") (class "Default")
      (node (ref "U6") (pin "7") (pinfunction "INT_7") (pintype "passive+no_connect"))
    )
    (net (code "79") (name "unconnected-(X1-COM_2-Pad4)") (class "Default")
      (node (ref "X1") (pin "4") (pinfunction "COM_2_4") (pintype "passive+no_connect"))
    )
    (net (code "80") (name "unconnected-(X1-NO_2-Pad3)") (class "Default")
      (node (ref "X1") (pin "3") (pinfunction "NO_2_3") (pintype "passive+no_connect"))
    )
  )
)
